# lpg_v21_4hp.net
KiCad netlist of a schematic drawn in EAGLE
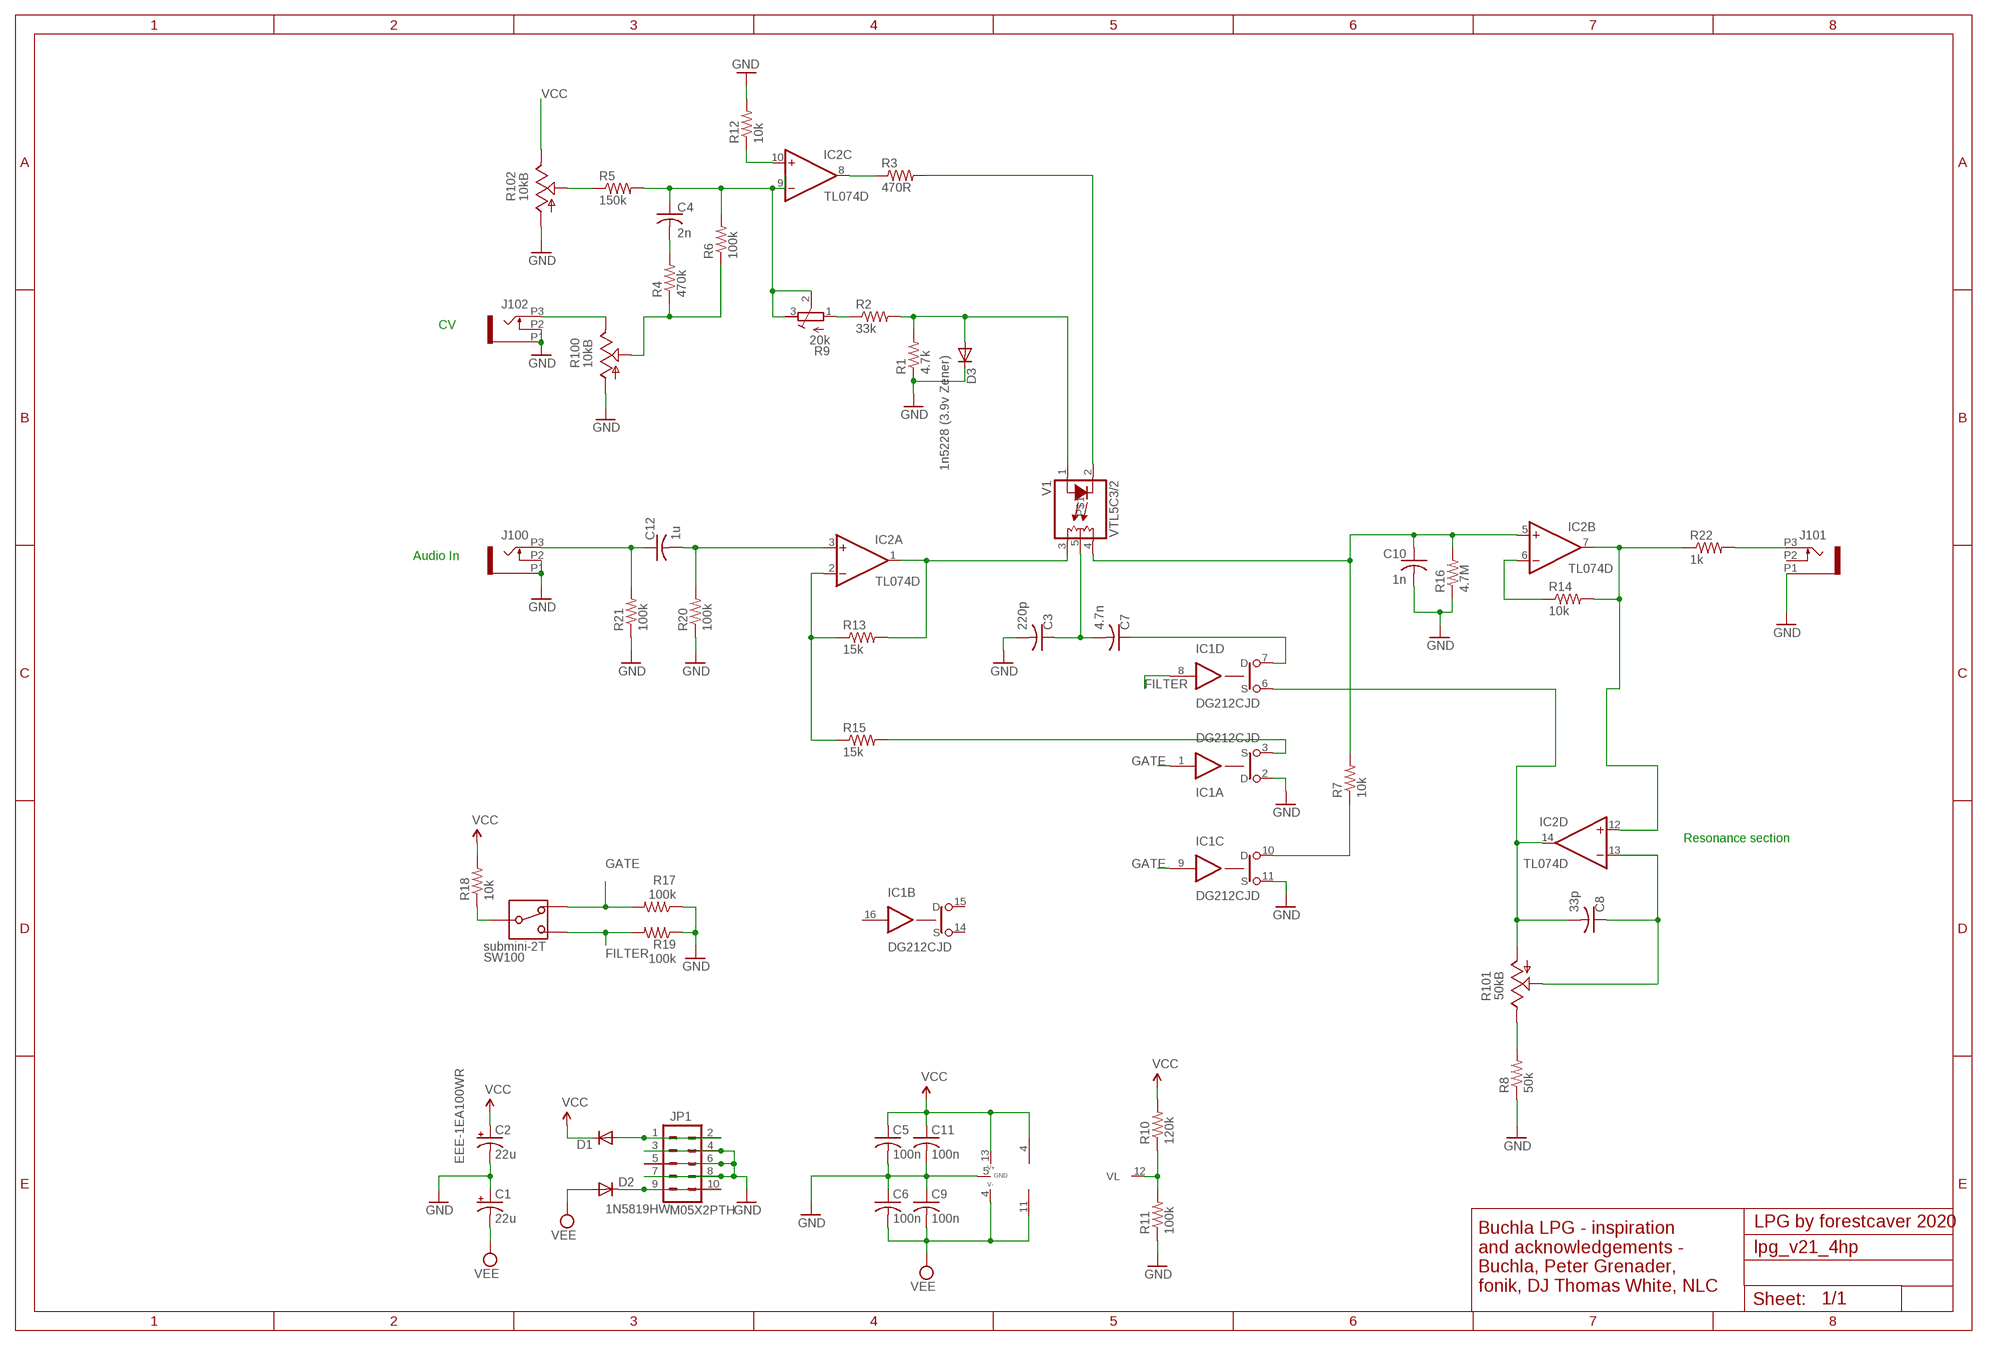
[diagram p0: schematic, sheet 1]

(export (version "E")
  (design (tool "Eeschema 10.0.6"))
  (components
    (comp (ref "C1")
      (value "22u")
      (footprint "eagle-import:PANASONIC_B")
      (fields (field (name "MPN") "EEE-FT1V220AR"))
      (libsource (lib "eagle-import") (part "CPOL-USB"))
    )
    (comp (ref "C2")
      (value "22u")
      (footprint "eagle-import:PANASONIC_B")
      (fields (field (name "MPN") "EEE-FT1V220AR"))
      (libsource (lib "eagle-import") (part "CPOL-USB"))
    )
    (comp (ref "C3")
      (value "220p")
      (footprint "eagle-import:C0603")
      (libsource (lib "eagle-import") (part "rcl_334_C-USC0603"))
    )
    (comp (ref "C4")
      (value "2n")
      (footprint "eagle-import:C0603")
      (libsource (lib "eagle-import") (part "rcl_334_C-USC0603"))
    )
    (comp (ref "C5")
      (value "100n")
      (footprint "eagle-import:C0603")
      (libsource (lib "eagle-import") (part "C-USC0603"))
    )
    (comp (ref "C6")
      (value "100n")
      (footprint "eagle-import:C0603")
      (libsource (lib "eagle-import") (part "C-USC0603"))
    )
    (comp (ref "C7")
      (value "4.7n")
      (footprint "eagle-import:C0603")
      (libsource (lib "eagle-import") (part "rcl_334_C-USC0603"))
    )
    (comp (ref "C8")
      (value "33p")
      (footprint "eagle-import:C0603")
      (libsource (lib "eagle-import") (part "rcl_334_C-USC0603"))
    )
    (comp (ref "C9")
      (value "100n")
      (footprint "eagle-import:C0603")
      (libsource (lib "eagle-import") (part "C-USC0603"))
    )
    (comp (ref "C10")
      (value "1n")
      (footprint "eagle-import:C0603")
      (libsource (lib "eagle-import") (part "rcl_334_C-USC0603"))
    )
    (comp (ref "C11")
      (value "100n")
      (footprint "eagle-import:C0603")
      (libsource (lib "eagle-import") (part "C-USC0603"))
    )
    (comp (ref "C12")
      (value "1u")
      (footprint "eagle-import:C0603")
      (libsource (lib "eagle-import") (part "rcl_334_C-USC0603"))
    )
    (comp (ref "D1")
      (value "1N5819HW")
      (footprint "eagle-import:SOD123")
      (libsource (lib "eagle-import") (part "DIODE-SOD123"))
    )
    (comp (ref "D2")
      (value "1N5819HW")
      (footprint "eagle-import:SOD123")
      (libsource (lib "eagle-import") (part "DIODE-SOD123"))
    )
    (comp (ref "D3")
      (value "1n5228 (3.9v Zener)")
      (footprint "eagle-import:SOD123")
      (fields (field (name "MPN") "MMSZ5228BT1G"))
      (libsource (lib "eagle-import") (part "DIODE-SOD123"))
    )
    (comp (ref "IC1")
      (value "DG212CJD")
      (footprint "eagle-import:SO16")
      (fields (field (name "MOUSER") "584-ADG212AKRZ-R") (field (name "MPN") "ADG212AKRZ-REEL"))
      (libsource (lib "eagle-import") (part "DG212CJD"))
    )
    (comp (ref "IC2")
      (value "TL074D")
      (footprint "eagle-import:SO14")
      (fields (field (name "MOUSER") "595-TL074CDR") (field (name "MPN") "TL074CDR"))
      (libsource (lib "eagle-import") (part "TL074D"))
    )
    (comp (ref "J100")
      (value "PJ301_THONKICONN6")
      (footprint "eagle-import:WQP_PJ_301M6")
      (libsource (lib "eagle-import") (part "PJ301_THONKICONN6"))
    )
    (comp (ref "J101")
      (value "PJ301_THONKICONN6")
      (footprint "eagle-import:WQP_PJ_301M6")
      (libsource (lib "eagle-import") (part "PJ301_THONKICONN6"))
    )
    (comp (ref "J102")
      (value "PJ301_THONKICONN6")
      (footprint "eagle-import:WQP_PJ_301M6")
      (libsource (lib "eagle-import") (part "PJ301_THONKICONN6"))
    )
    (comp (ref "JP1")
      (value "M05X2PTH")
      (footprint "eagle-import:AVR_ICSP")
      (libsource (lib "eagle-import") (part "M05X2PTH"))
    )
    (comp (ref "R1")
      (value "4.7k")
      (footprint "eagle-import:R0603")
      (libsource (lib "eagle-import") (part "R-US_R0603"))
    )
    (comp (ref "R2")
      (value "33k")
      (footprint "eagle-import:R0603")
      (libsource (lib "eagle-import") (part "R-US_R0603"))
    )
    (comp (ref "R3")
      (value "470R")
      (footprint "eagle-import:R0603")
      (libsource (lib "eagle-import") (part "R-US_R0603"))
    )
    (comp (ref "R4")
      (value "470k")
      (footprint "eagle-import:R0603")
      (libsource (lib "eagle-import") (part "R-US_R0603"))
    )
    (comp (ref "R5")
      (value "150k")
      (footprint "eagle-import:R0603")
      (libsource (lib "eagle-import") (part "R-US_R0603"))
    )
    (comp (ref "R6")
      (value "100k")
      (footprint "eagle-import:R0603")
      (libsource (lib "eagle-import") (part "R-US_R0603"))
    )
    (comp (ref "R7")
      (value "10k")
      (footprint "eagle-import:R0603")
      (libsource (lib "eagle-import") (part "R-US_R0603"))
    )
    (comp (ref "R8")
      (value "50k")
      (footprint "eagle-import:R0603")
      (libsource (lib "eagle-import") (part "R-US_R0603"))
    )
    (comp (ref "R9")
      (value "20k")
      (footprint "eagle-import:RTRIM3296X")
      (libsource (lib "eagle-import") (part "R-TRIMM3296X"))
    )
    (comp (ref "R10")
      (value "120k")
      (footprint "eagle-import:R0603")
      (libsource (lib "eagle-import") (part "R-US_R0603"))
    )
    (comp (ref "R11")
      (value "100k")
      (footprint "eagle-import:R0603")
      (libsource (lib "eagle-import") (part "R-US_R0603"))
    )
    (comp (ref "R12")
      (value "10k")
      (footprint "eagle-import:R0603")
      (libsource (lib "eagle-import") (part "R-US_R0603"))
    )
    (comp (ref "R13")
      (value "15k")
      (footprint "eagle-import:R0603")
      (libsource (lib "eagle-import") (part "R-US_R0603"))
    )
    (comp (ref "R14")
      (value "10k")
      (footprint "eagle-import:R0603")
      (libsource (lib "eagle-import") (part "R-US_R0603"))
    )
    (comp (ref "R15")
      (value "15k")
      (footprint "eagle-import:R0603")
      (libsource (lib "eagle-import") (part "R-US_R0603"))
    )
    (comp (ref "R16")
      (value "4.7M")
      (footprint "eagle-import:R0603")
      (libsource (lib "eagle-import") (part "R-US_R0603"))
    )
    (comp (ref "R17")
      (value "100k")
      (footprint "eagle-import:R0603")
      (libsource (lib "eagle-import") (part "R-US_R0603"))
    )
    (comp (ref "R18")
      (value "10k")
      (footprint "eagle-import:R0603")
      (libsource (lib "eagle-import") (part "R-US_R0603"))
    )
    (comp (ref "R19")
      (value "100k")
      (footprint "eagle-import:R0603")
      (libsource (lib "eagle-import") (part "R-US_R0603"))
    )
    (comp (ref "R20")
      (value "100k")
      (footprint "eagle-import:R0603")
      (libsource (lib "eagle-import") (part "R-US_R0603"))
    )
    (comp (ref "R21")
      (value "100k")
      (footprint "eagle-import:R0603")
      (libsource (lib "eagle-import") (part "R-US_R0603"))
    )
    (comp (ref "R22")
      (value "1k")
      (footprint "eagle-import:R0603")
      (libsource (lib "eagle-import") (part "R-US_R0603"))
    )
    (comp (ref "R100")
      (value "10kB")
      (footprint "eagle-import:ALPS_POT_VERTICAL_PS")
      (libsource (lib "eagle-import") (part "POT_USVERTICAL_PS"))
    )
    (comp (ref "R101")
      (value "50kB")
      (footprint "eagle-import:ALPS_POT_VERTICAL_PS")
      (libsource (lib "eagle-import") (part "POT_USVERTICAL_PS"))
    )
    (comp (ref "R102")
      (value "10kB")
      (footprint "eagle-import:ALPS_POT_VERTICAL_PS")
      (libsource (lib "eagle-import") (part "POT_USVERTICAL_PS"))
    )
    (comp (ref "SW100")
      (value "submini-2T")
      (footprint "eagle-import:SPDT-SUB")
      (libsource (lib "eagle-import") (part "SPDTT"))
    )
    (comp (ref "V1")
      (value "VTL5C3/2")
      (footprint "eagle-import:VACTROL_5PIN_VTL5C-2")
      (libsource (lib "eagle-import") (part "VACTROL_5PIN"))
    )
  )
  (nets
    (net (code "1") (name "/FILTER") (class "Default")
      (node (ref "IC1") (pin "8") (pinfunction "IN_8") (pintype "input"))
      (node (ref "R19") (pin "2") (pinfunction "2_2") (pintype "passive"))
      (node (ref "SW100") (pin "P$1") (pinfunction "P$1_P$1") (pintype "passive"))
    )
    (net (code "2") (name "/GATE") (class "Default")
      (node (ref "IC1") (pin "1") (pinfunction "IN_1") (pintype "input"))
      (node (ref "IC1") (pin "9") (pinfunction "IN_9") (pintype "input"))
      (node (ref "R17") (pin "2") (pinfunction "2_2") (pintype "passive"))
      (node (ref "SW100") (pin "P$3") (pinfunction "P$3_P$3") (pintype "passive"))
    )
    (net (code "3") (name "GND") (class "Default")
      (node (ref "C1") (pin "+") (pinfunction "+_+") (pintype "passive"))
      (node (ref "C10") (pin "2") (pinfunction "2_2") (pintype "passive"))
      (node (ref "C11") (pin "2") (pinfunction "2_2") (pintype "passive"))
      (node (ref "C2") (pin "-") (pinfunction "-_-") (pintype "passive"))
      (node (ref "C3") (pin "2") (pinfunction "2_2") (pintype "passive"))
      (node (ref "C5") (pin "2") (pinfunction "2_2") (pintype "passive"))
      (node (ref "C6") (pin "1") (pinfunction "1_1") (pintype "passive"))
      (node (ref "C9") (pin "1") (pinfunction "1_1") (pintype "passive"))
      (node (ref "D3") (pin "C") (pinfunction "C_C") (pintype "passive"))
      (node (ref "IC1") (pin "11") (pinfunction "S_11") (pintype "bidirectional"))
      (node (ref "IC1") (pin "2") (pinfunction "D_2") (pintype "bidirectional"))
      (node (ref "IC1") (pin "5") (pinfunction "GND_5") (pintype "power_in"))
      (node (ref "J100") (pin "P1") (pinfunction "1_P1") (pintype "passive"))
      (node (ref "J100") (pin "P2") (pinfunction "2_P2") (pintype "passive"))
      (node (ref "J101") (pin "P1") (pinfunction "1_P1") (pintype "passive"))
      (node (ref "J102") (pin "P1") (pinfunction "1_P1") (pintype "passive"))
      (node (ref "J102") (pin "P2") (pinfunction "2_P2") (pintype "passive"))
      (node (ref "JP1") (pin "3") (pinfunction "3_3") (pintype "passive"))
      (node (ref "JP1") (pin "4") (pinfunction "4_4") (pintype "passive"))
      (node (ref "JP1") (pin "5") (pinfunction "5_5") (pintype "passive"))
      (node (ref "JP1") (pin "6") (pinfunction "6_6") (pintype "passive"))
      (node (ref "JP1") (pin "7") (pinfunction "7_7") (pintype "passive"))
      (node (ref "JP1") (pin "8") (pinfunction "8_8") (pintype "passive"))
      (node (ref "R1") (pin "1") (pinfunction "1_1") (pintype "passive"))
      (node (ref "R100") (pin "P$3") (pinfunction "A_P$3") (pintype "passive"))
      (node (ref "R102") (pin "P$3") (pinfunction "A_P$3") (pintype "passive"))
      (node (ref "R11") (pin "1") (pinfunction "1_1") (pintype "passive"))
      (node (ref "R12") (pin "2") (pinfunction "2_2") (pintype "passive"))
      (node (ref "R16") (pin "1") (pinfunction "1_1") (pintype "passive"))
      (node (ref "R17") (pin "1") (pinfunction "1_1") (pintype "passive"))
      (node (ref "R19") (pin "1") (pinfunction "1_1") (pintype "passive"))
      (node (ref "R20") (pin "1") (pinfunction "1_1") (pintype "passive"))
      (node (ref "R21") (pin "1") (pinfunction "1_1") (pintype "passive"))
      (node (ref "R8") (pin "1") (pinfunction "1_1") (pintype "passive"))
    )
    (net (code "4") (name "Net-(C4-Pad2)") (class "Default")
      (node (ref "C4") (pin "2") (pinfunction "2_2") (pintype "passive"))
      (node (ref "R4") (pin "2") (pinfunction "2_2") (pintype "passive"))
    )
    (net (code "5") (name "Net-(D1-PadA)") (class "Default")
      (node (ref "D1") (pin "A") (pinfunction "A_A") (pintype "passive"))
      (node (ref "JP1") (pin "1") (pinfunction "1_1") (pintype "passive"))
      (node (ref "JP1") (pin "2") (pinfunction "2_2") (pintype "passive"))
    )
    (net (code "6") (name "Net-(D2-PadC)") (class "Default")
      (node (ref "D2") (pin "C") (pinfunction "C_C") (pintype "passive"))
      (node (ref "JP1") (pin "10") (pinfunction "10_10") (pintype "passive"))
      (node (ref "JP1") (pin "9") (pinfunction "9_9") (pintype "passive"))
    )
    (net (code "7") (name "Net-(IC1A-S)") (class "Default")
      (node (ref "IC1") (pin "3") (pinfunction "S_3") (pintype "bidirectional"))
      (node (ref "R15") (pin "2") (pinfunction "2_2") (pintype "passive"))
    )
    (net (code "8") (name "Net-(IC1C-D)") (class "Default")
      (node (ref "IC1") (pin "10") (pinfunction "D_10") (pintype "bidirectional"))
      (node (ref "R7") (pin "1") (pinfunction "1_1") (pintype "passive"))
    )
    (net (code "9") (name "Net-(IC1D-D)") (class "Default")
      (node (ref "C7") (pin "1") (pinfunction "1_1") (pintype "passive"))
      (node (ref "IC1") (pin "7") (pinfunction "D_7") (pintype "bidirectional"))
    )
    (net (code "10") (name "Net-(IC1D-S)") (class "Default")
      (node (ref "C8") (pin "2") (pinfunction "2_2") (pintype "passive"))
      (node (ref "IC1") (pin "6") (pinfunction "S_6") (pintype "bidirectional"))
      (node (ref "IC2") (pin "14") (pinfunction "OUT_14") (pintype "output"))
      (node (ref "R101") (pin "P$3") (pinfunction "A_P$3") (pintype "passive"))
    )
    (net (code "11") (name "Net-(IC1F-VL)") (class "Default")
      (node (ref "IC1") (pin "12") (pinfunction "VL_12") (pintype "input"))
      (node (ref "R10") (pin "1") (pinfunction "1_1") (pintype "passive"))
      (node (ref "R11") (pin "2") (pinfunction "2_2") (pintype "passive"))
    )
    (net (code "12") (name "Net-(IC2A-+IN)") (class "Default")
      (node (ref "C12") (pin "2") (pinfunction "2_2") (pintype "passive"))
      (node (ref "IC2") (pin "3") (pinfunction "+IN_3") (pintype "input"))
      (node (ref "R20") (pin "2") (pinfunction "2_2") (pintype "passive"))
    )
    (net (code "13") (name "Net-(IC2A--IN)") (class "Default")
      (node (ref "IC2") (pin "2") (pinfunction "-IN_2") (pintype "input"))
      (node (ref "R13") (pin "1") (pinfunction "1_1") (pintype "passive"))
      (node (ref "R15") (pin "1") (pinfunction "1_1") (pintype "passive"))
    )
    (net (code "14") (name "Net-(IC2A-OUT)") (class "Default")
      (node (ref "IC2") (pin "1") (pinfunction "OUT_1") (pintype "output"))
      (node (ref "R13") (pin "2") (pinfunction "2_2") (pintype "passive"))
      (node (ref "V1") (pin "3") (pinfunction "L1_3") (pintype "passive"))
    )
    (net (code "15") (name "Net-(IC2B-+IN)") (class "Default")
      (node (ref "C10") (pin "1") (pinfunction "1_1") (pintype "passive"))
      (node (ref "IC2") (pin "5") (pinfunction "+IN_5") (pintype "input"))
      (node (ref "R16") (pin "2") (pinfunction "2_2") (pintype "passive"))
      (node (ref "R7") (pin "2") (pinfunction "2_2") (pintype "passive"))
      (node (ref "V1") (pin "4") (pinfunction "L2_4") (pintype "passive"))
    )
    (net (code "16") (name "Net-(IC2B--IN)") (class "Default")
      (node (ref "IC2") (pin "6") (pinfunction "-IN_6") (pintype "input"))
      (node (ref "R14") (pin "1") (pinfunction "1_1") (pintype "passive"))
    )
    (net (code "17") (name "Net-(IC2B-OUT)") (class "Default")
      (node (ref "IC2") (pin "12") (pinfunction "+IN_12") (pintype "input"))
      (node (ref "IC2") (pin "7") (pinfunction "OUT_7") (pintype "output"))
      (node (ref "R14") (pin "2") (pinfunction "2_2") (pintype "passive"))
      (node (ref "R22") (pin "1") (pinfunction "1_1") (pintype "passive"))
    )
    (net (code "18") (name "Net-(IC2C-+IN)") (class "Default")
      (node (ref "IC2") (pin "10") (pinfunction "+IN_10") (pintype "input"))
      (node (ref "R12") (pin "1") (pinfunction "1_1") (pintype "passive"))
    )
    (net (code "19") (name "Net-(IC2C--IN)") (class "Default")
      (node (ref "C4") (pin "1") (pinfunction "1_1") (pintype "passive"))
      (node (ref "IC2") (pin "9") (pinfunction "-IN_9") (pintype "input"))
      (node (ref "R5") (pin "2") (pinfunction "2_2") (pintype "passive"))
      (node (ref "R6") (pin "2") (pinfunction "2_2") (pintype "passive"))
      (node (ref "R9") (pin "2") (pinfunction "S_2") (pintype "passive"))
      (node (ref "R9") (pin "3") (pinfunction "A_3") (pintype "passive"))
    )
    (net (code "20") (name "Net-(IC2C-OUT)") (class "Default")
      (node (ref "IC2") (pin "8") (pinfunction "OUT_8") (pintype "output"))
      (node (ref "R3") (pin "1") (pinfunction "1_1") (pintype "passive"))
    )
    (net (code "21") (name "Net-(IC2D--IN)") (class "Default")
      (node (ref "C8") (pin "1") (pinfunction "1_1") (pintype "passive"))
      (node (ref "IC2") (pin "13") (pinfunction "-IN_13") (pintype "input"))
      (node (ref "R101") (pin "P$2") (pinfunction "S_P$2") (pintype "passive"))
    )
    (net (code "22") (name "Net-(J100-3)") (class "Default")
      (node (ref "C12") (pin "1") (pinfunction "1_1") (pintype "passive"))
      (node (ref "J100") (pin "P3") (pinfunction "3_P3") (pintype "passive"))
      (node (ref "R21") (pin "2") (pinfunction "2_2") (pintype "passive"))
    )
    (net (code "23") (name "Net-(J101-3)") (class "Default")
      (node (ref "J101") (pin "P3") (pinfunction "3_P3") (pintype "passive"))
      (node (ref "R22") (pin "2") (pinfunction "2_2") (pintype "passive"))
    )
    (net (code "24") (name "Net-(J102-3)") (class "Default")
      (node (ref "J102") (pin "P3") (pinfunction "3_P3") (pintype "passive"))
      (node (ref "R100") (pin "P$1") (pinfunction "E_P$1") (pintype "passive"))
    )
    (net (code "25") (name "Net-(R9-E)") (class "Default")
      (node (ref "R2") (pin "1") (pinfunction "1_1") (pintype "passive"))
      (node (ref "R9") (pin "1") (pinfunction "E_1") (pintype "passive"))
    )
    (net (code "26") (name "Net-(R18-Pad1)") (class "Default")
      (node (ref "R18") (pin "1") (pinfunction "1_1") (pintype "passive"))
      (node (ref "SW100") (pin "P$2") (pinfunction "P$2_P$2") (pintype "passive"))
    )
    (net (code "27") (name "Net-(R100-S)") (class "Default")
      (node (ref "R100") (pin "P$2") (pinfunction "S_P$2") (pintype "passive"))
      (node (ref "R4") (pin "1") (pinfunction "1_1") (pintype "passive"))
      (node (ref "R6") (pin "1") (pinfunction "1_1") (pintype "passive"))
    )
    (net (code "28") (name "Net-(R101-E)") (class "Default")
      (node (ref "R101") (pin "P$1") (pinfunction "E_P$1") (pintype "passive"))
      (node (ref "R8") (pin "2") (pinfunction "2_2") (pintype "passive"))
    )
    (net (code "29") (name "Net-(R102-S)") (class "Default")
      (node (ref "R102") (pin "P$2") (pinfunction "S_P$2") (pintype "passive"))
      (node (ref "R5") (pin "1") (pinfunction "1_1") (pintype "passive"))
    )
    (net (code "30") (name "Net-(V1-A)") (class "Default")
      (node (ref "D3") (pin "A") (pinfunction "A_A") (pintype "passive"))
      (node (ref "R1") (pin "2") (pinfunction "2_2") (pintype "passive"))
      (node (ref "R2") (pin "2") (pinfunction "2_2") (pintype "passive"))
      (node (ref "V1") (pin "1") (pinfunction "A_1") (pintype "passive"))
    )
    (net (code "31") (name "Net-(V1-C)") (class "Default")
      (node (ref "R3") (pin "2") (pinfunction "2_2") (pintype "passive"))
      (node (ref "V1") (pin "2") (pinfunction "C_2") (pintype "passive"))
    )
    (net (code "32") (name "Net-(V1-P$1)") (class "Default")
      (node (ref "C3") (pin "1") (pinfunction "1_1") (pintype "passive"))
      (node (ref "C7") (pin "2") (pinfunction "2_2") (pintype "passive"))
      (node (ref "V1") (pin "5") (pinfunction "P$1_5") (pintype "passive"))
    )
    (net (code "33") (name "VCC") (class "Default")
      (node (ref "C11") (pin "1") (pinfunction "1_1") (pintype "passive"))
      (node (ref "C2") (pin "+") (pinfunction "+_+") (pintype "passive"))
      (node (ref "C5") (pin "1") (pinfunction "1_1") (pintype "passive"))
      (node (ref "D1") (pin "C") (pinfunction "C_C") (pintype "passive"))
      (node (ref "IC1") (pin "13") (pinfunction "V+_13") (pintype "power_in"))
      (node (ref "IC2") (pin "4") (pinfunction "V+_4") (pintype "power_in"))
      (node (ref "R10") (pin "2") (pinfunction "2_2") (pintype "passive"))
      (node (ref "R102") (pin "P$1") (pinfunction "E_P$1") (pintype "passive"))
      (node (ref "R18") (pin "2") (pinfunction "2_2") (pintype "passive"))
    )
    (net (code "34") (name "VEE") (class "Default")
      (node (ref "C1") (pin "-") (pinfunction "-_-") (pintype "passive"))
      (node (ref "C6") (pin "2") (pinfunction "2_2") (pintype "passive"))
      (node (ref "C9") (pin "2") (pinfunction "2_2") (pintype "passive"))
      (node (ref "D2") (pin "A") (pinfunction "A_A") (pintype "passive"))
      (node (ref "IC1") (pin "4") (pinfunction "V-_4") (pintype "power_in"))
      (node (ref "IC2") (pin "11") (pinfunction "V-_11") (pintype "power_in"))
    )
    (net (code "35") (name "unconnected-(IC1B-D-Pad15)") (class "Default")
      (node (ref "IC1") (pin "15") (pinfunction "D_15") (pintype "bidirectional"))
    )
    (net (code "36") (name "unconnected-(IC1B-IN-Pad16)") (class "Default")
      (node (ref "IC1") (pin "16") (pinfunction "IN_16") (pintype "input"))
    )
    (net (code "37") (name "unconnected-(IC1B-S-Pad14)") (class "Default")
      (node (ref "IC1") (pin "14") (pinfunction "S_14") (pintype "bidirectional"))
    )
    (net (code "38") (name "unconnected-(J101-2-PadP2)") (class "Default")
      (node (ref "J101") (pin "P2") (pinfunction "2_P2") (pintype "passive"))
    )
  )
)
